# 1_Main.net
KiCad netlist of a schematic drawn in EAGLE
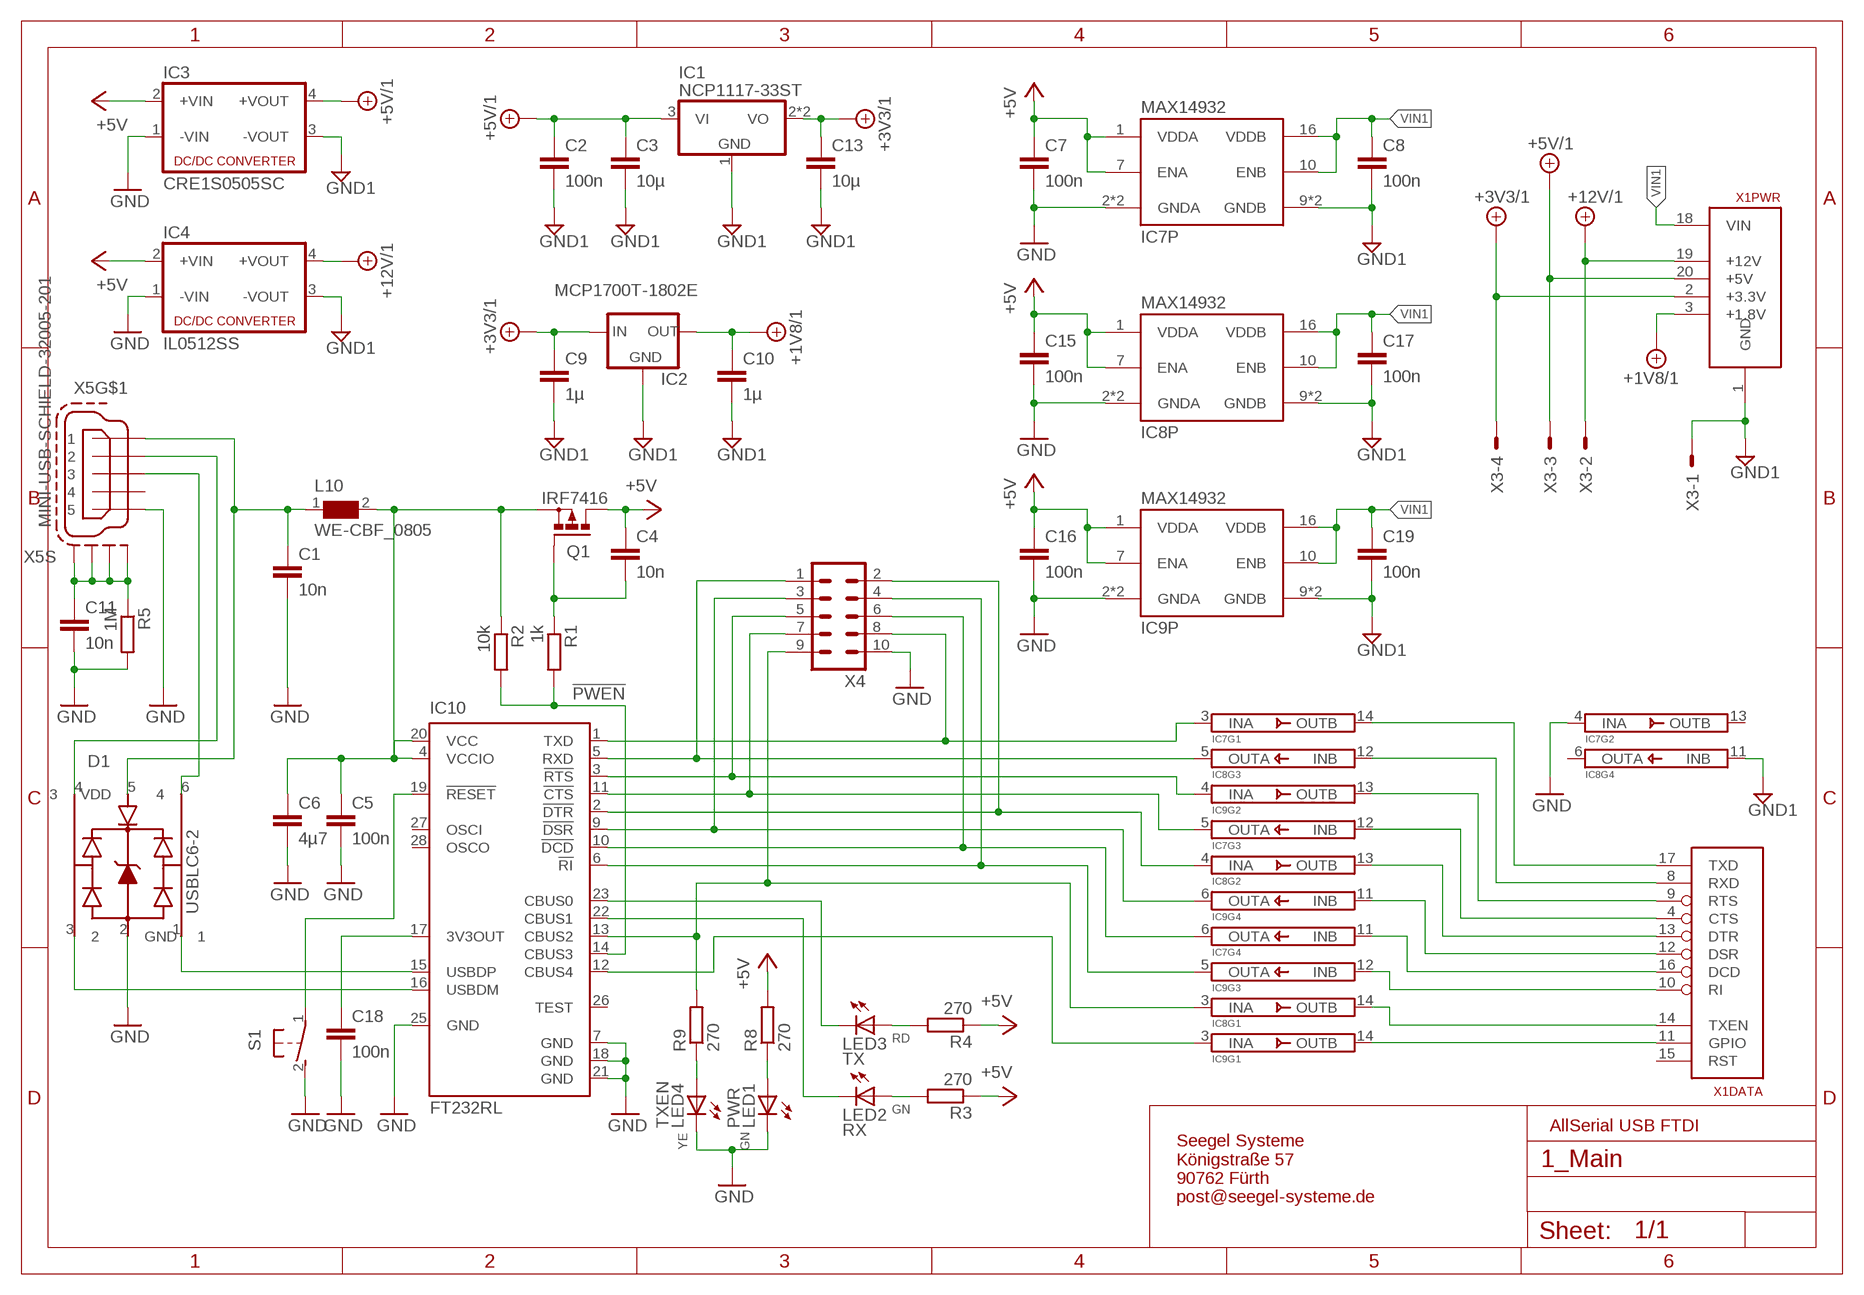
[diagram p0: schematic, sheet 1]

(export (version "E")
  (design (tool "Eeschema 10.0.6"))
  (components
    (comp (ref "C1")
      (value "10n")
      (footprint "eagle-import:C0805")
      (libsource (lib "eagle-import") (part "C-EUC0805"))
    )
    (comp (ref "C2")
      (value "100n")
      (footprint "eagle-import:C0805")
      (libsource (lib "eagle-import") (part "C-EUC0805"))
    )
    (comp (ref "C3")
      (value "10µ")
      (footprint "eagle-import:C0805")
      (libsource (lib "eagle-import") (part "C-EUC0805"))
    )
    (comp (ref "C4")
      (value "10n")
      (footprint "eagle-import:C0805")
      (libsource (lib "eagle-import") (part "C-EUC0805"))
    )
    (comp (ref "C5")
      (value "100n")
      (footprint "eagle-import:C0805")
      (libsource (lib "eagle-import") (part "C-EUC0805"))
    )
    (comp (ref "C6")
      (value "4µ7")
      (footprint "eagle-import:C0805")
      (libsource (lib "eagle-import") (part "C-EUC0805"))
    )
    (comp (ref "C7")
      (value "100n")
      (footprint "eagle-import:C0805")
      (libsource (lib "eagle-import") (part "C-EUC0805"))
    )
    (comp (ref "C8")
      (value "100n")
      (footprint "eagle-import:C0805")
      (libsource (lib "eagle-import") (part "C-EUC0805"))
    )
    (comp (ref "C9")
      (value "1µ")
      (footprint "eagle-import:C0805")
      (libsource (lib "eagle-import") (part "C-EUC0805"))
    )
    (comp (ref "C10")
      (value "1µ")
      (footprint "eagle-import:C0805")
      (libsource (lib "eagle-import") (part "C-EUC0805"))
    )
    (comp (ref "C11")
      (value "10n")
      (footprint "eagle-import:C0805")
      (libsource (lib "eagle-import") (part "C-EUC0805"))
    )
    (comp (ref "C13")
      (value "10µ")
      (footprint "eagle-import:C0805")
      (libsource (lib "eagle-import") (part "C-EUC0805"))
    )
    (comp (ref "C15")
      (value "100n")
      (footprint "eagle-import:C0805")
      (libsource (lib "eagle-import") (part "C-EUC0805"))
    )
    (comp (ref "C16")
      (value "100n")
      (footprint "eagle-import:C0805")
      (libsource (lib "eagle-import") (part "C-EUC0805"))
    )
    (comp (ref "C17")
      (value "100n")
      (footprint "eagle-import:C0805")
      (libsource (lib "eagle-import") (part "C-EUC0805"))
    )
    (comp (ref "C18")
      (value "100n")
      (footprint "eagle-import:C0805")
      (libsource (lib "eagle-import") (part "C-EUC0805"))
    )
    (comp (ref "C19")
      (value "100n")
      (footprint "eagle-import:C0805")
      (libsource (lib "eagle-import") (part "C-EUC0805"))
    )
    (comp (ref "D1")
      (value "USBLC6-2")
      (footprint "eagle-import:WE-TVS_SOT23-6L")
      (libsource (lib "eagle-import") (part "WE-TVS_82400102"))
    )
    (comp (ref "IC1")
      (value "NCP1117-33ST")
      (footprint "eagle-import:SOT223")
      (libsource (lib "eagle-import") (part "NCP1117ST-33"))
    )
    (comp (ref "IC2")
      (value "MCP1700T-1802E")
      (footprint "eagle-import:SOT23")
      (libsource (lib "eagle-import") (part "MCP170X"))
    )
    (comp (ref "IC3")
      (value "CRE1S0505SC")
      (footprint "eagle-import:MURATA-SC")
      (libsource (lib "eagle-import") (part "CRE1S?SC0505"))
    )
    (comp (ref "IC4")
      (value "IL0512SS")
      (footprint "eagle-import:XPPOWER-SIP")
      (libsource (lib "eagle-import") (part "ILSS0512"))
    )
    (comp (ref "IC7")
      (value "MAX14932")
      (footprint "eagle-import:SO16")
      (libsource (lib "eagle-import") (part "MAX14932"))
    )
    (comp (ref "IC8")
      (value "MAX14932")
      (footprint "eagle-import:SO16")
      (libsource (lib "eagle-import") (part "MAX14932"))
    )
    (comp (ref "IC9")
      (value "MAX14932")
      (footprint "eagle-import:SO16")
      (libsource (lib "eagle-import") (part "MAX14932"))
    )
    (comp (ref "IC10")
      (value "FT232RL")
      (footprint "eagle-import:SSOP28")
      (libsource (lib "eagle-import") (part "FT232RL"))
    )
    (comp (ref "L10")
      (value "WE-CBF_0805")
      (footprint "eagle-import:0805")
      (libsource (lib "eagle-import") (part "WE-CBF_0805"))
    )
    (comp (ref "LED1")
      (value "PWR")
      (footprint "eagle-import:CHIPLED_0603")
      (fields (field (name "COLOR") "GN"))
      (libsource (lib "eagle-import") (part "LEDCHIPLED_0603"))
    )
    (comp (ref "LED2")
      (value "RX")
      (footprint "eagle-import:CHIPLED_0603")
      (fields (field (name "COLOR") "GN"))
      (libsource (lib "eagle-import") (part "LEDCHIPLED_0603"))
    )
    (comp (ref "LED3")
      (value "TX")
      (footprint "eagle-import:CHIPLED_0603")
      (fields (field (name "COLOR") "RD"))
      (libsource (lib "eagle-import") (part "LEDCHIPLED_0603"))
    )
    (comp (ref "LED4")
      (value "TXEN")
      (footprint "eagle-import:CHIPLED_0603")
      (fields (field (name "COLOR") "YE"))
      (libsource (lib "eagle-import") (part "LEDCHIPLED_0603"))
    )
    (comp (ref "Q1")
      (value "IRF7416")
      (footprint "eagle-import:SO-08")
      (libsource (lib "eagle-import") (part "P-MOSFET-SO8"))
    )
    (comp (ref "R1")
      (value "1k")
      (footprint "eagle-import:R0805")
      (libsource (lib "eagle-import") (part "R-EU_R0805"))
    )
    (comp (ref "R2")
      (value "10k")
      (footprint "eagle-import:R0805")
      (libsource (lib "eagle-import") (part "R-EU_R0805"))
    )
    (comp (ref "R3")
      (value "270")
      (footprint "eagle-import:R0805")
      (libsource (lib "eagle-import") (part "R-EU_R0805"))
    )
    (comp (ref "R4")
      (value "270")
      (footprint "eagle-import:R0805")
      (libsource (lib "eagle-import") (part "R-EU_R0805"))
    )
    (comp (ref "R5")
      (value "1M")
      (footprint "eagle-import:R0805")
      (libsource (lib "eagle-import") (part "R-EU_R0805"))
    )
    (comp (ref "R8")
      (value "270")
      (footprint "eagle-import:R0805")
      (libsource (lib "eagle-import") (part "R-EU_R0805"))
    )
    (comp (ref "R9")
      (value "270")
      (footprint "eagle-import:R0805")
      (libsource (lib "eagle-import") (part "R-EU_R0805"))
    )
    (comp (ref "S1")
      (value "31-XX")
      (footprint "eagle-import:B3F-31XX")
      (fields (field (name "MPN") "B3F-3100"))
      (libsource (lib "eagle-import") (part "31-XX"))
    )
    (comp (ref "X1")
      (value "ALLSERIALMASTERMM")
      (footprint "eagle-import:MAIN-THT")
      (libsource (lib "eagle-import") (part "ALLSERIALMASTERMM"))
    )
    (comp (ref "X3")
      (value "AKL18X-04W")
      (footprint "eagle-import:AKL182-04")
      (libsource (lib "eagle-import") (part "AKL18X-04W"))
    )
    (comp (ref "X4")
      (value "ML10")
      (footprint "eagle-import:ML10")
      (libsource (lib "eagle-import") (part "ML10"))
    )
    (comp (ref "X5")
      (value "MINI-USB-SCHIELD-32005-201")
      (footprint "eagle-import:32005-201")
      (libsource (lib "eagle-import") (part "MINI-USB-SCHIELD-32005-201"))
    )
  )
  (nets
    (net (code "1") (name "+1V8{slash}1") (class "Default")
      (node (ref "C10") (pin "1") (pinfunction "1_1") (pintype "passive"))
      (node (ref "IC2") (pin "2") (pinfunction "OUT_2") (pintype "passive"))
      (node (ref "X1") (pin "3") (pinfunction "+1.8V_3") (pintype "bidirectional"))
    )
    (net (code "2") (name "+3V3{slash}1") (class "Default")
      (node (ref "C13") (pin "1") (pinfunction "1_1") (pintype "passive"))
      (node (ref "C9") (pin "1") (pinfunction "1_1") (pintype "passive"))
      (node (ref "IC1") (pin "2") (pinfunction "VO_2") (pintype "passive"))
      (node (ref "IC1") (pin "4") (pinfunction "VO_4") (pintype "passive"))
      (node (ref "IC2") (pin "3") (pinfunction "IN_3") (pintype "input"))
      (node (ref "X1") (pin "2") (pinfunction "+3.3V_2") (pintype "bidirectional"))
      (node (ref "X3") (pin "P$4") (pinfunction "S_P$4") (pintype "passive"))
    )
    (net (code "3") (name "+5V") (class "Default")
      (node (ref "C15") (pin "1") (pinfunction "1_1") (pintype "passive"))
      (node (ref "C16") (pin "1") (pinfunction "1_1") (pintype "passive"))
      (node (ref "C4") (pin "1") (pinfunction "1_1") (pintype "passive"))
      (node (ref "C7") (pin "1") (pinfunction "1_1") (pintype "passive"))
      (node (ref "IC3") (pin "2") (pinfunction "+VIN_2") (pintype "passive"))
      (node (ref "IC4") (pin "2") (pinfunction "+VIN_2") (pintype "passive"))
      (node (ref "IC7") (pin "1") (pinfunction "VDDA_1") (pintype "power_in"))
      (node (ref "IC7") (pin "7") (pinfunction "ENA_7") (pintype "input"))
      (node (ref "IC8") (pin "1") (pinfunction "VDDA_1") (pintype "power_in"))
      (node (ref "IC8") (pin "7") (pinfunction "ENA_7") (pintype "input"))
      (node (ref "IC9") (pin "1") (pinfunction "VDDA_1") (pintype "power_in"))
      (node (ref "IC9") (pin "7") (pinfunction "ENA_7") (pintype "input"))
      (node (ref "Q1") (pin "5") (pinfunction "D_5") (pintype "passive"))
      (node (ref "Q1") (pin "6") (pinfunction "D_6") (pintype "passive"))
      (node (ref "Q1") (pin "7") (pinfunction "D_7") (pintype "passive"))
      (node (ref "Q1") (pin "8") (pinfunction "D_8") (pintype "passive"))
      (node (ref "R3") (pin "1") (pinfunction "1_1") (pintype "passive"))
      (node (ref "R4") (pin "1") (pinfunction "1_1") (pintype "passive"))
      (node (ref "R8") (pin "2") (pinfunction "2_2") (pintype "passive"))
    )
    (net (code "4") (name "+5V{slash}1") (class "Default")
      (node (ref "C2") (pin "1") (pinfunction "1_1") (pintype "passive"))
      (node (ref "C3") (pin "1") (pinfunction "1_1") (pintype "passive"))
      (node (ref "IC1") (pin "3") (pinfunction "VI_3") (pintype "input"))
      (node (ref "IC3") (pin "4") (pinfunction "+VOUT_4") (pintype "passive"))
      (node (ref "X1") (pin "20") (pinfunction "+5V_20") (pintype "bidirectional"))
      (node (ref "X3") (pin "P$3") (pinfunction "S_P$3") (pintype "passive"))
    )
    (net (code "5") (name "+12V{slash}1") (class "Default")
      (node (ref "IC4") (pin "4") (pinfunction "+VOUT_4") (pintype "passive"))
      (node (ref "X1") (pin "19") (pinfunction "+12V_19") (pintype "bidirectional"))
      (node (ref "X3") (pin "P$2") (pinfunction "S_P$2") (pintype "passive"))
    )
    (net (code "6") (name "/~{PWEN}") (class "Default")
      (node (ref "IC10") (pin "14") (pinfunction "CBUS3_14") (pintype "bidirectional"))
      (node (ref "R1") (pin "2") (pinfunction "2_2") (pintype "passive"))
      (node (ref "R2") (pin "2") (pinfunction "2_2") (pintype "passive"))
    )
    (net (code "7") (name "GND") (class "Default")
      (node (ref "C1") (pin "2") (pinfunction "2_2") (pintype "passive"))
      (node (ref "C11") (pin "2") (pinfunction "2_2") (pintype "passive"))
      (node (ref "C15") (pin "2") (pinfunction "2_2") (pintype "passive"))
      (node (ref "C16") (pin "2") (pinfunction "2_2") (pintype "passive"))
      (node (ref "C18") (pin "2") (pinfunction "2_2") (pintype "passive"))
      (node (ref "C5") (pin "2") (pinfunction "2_2") (pintype "passive"))
      (node (ref "C6") (pin "2") (pinfunction "2_2") (pintype "passive"))
      (node (ref "C7") (pin "2") (pinfunction "2_2") (pintype "passive"))
      (node (ref "D1") (pin "2") (pinfunction "GND_2") (pintype "power_in"))
      (node (ref "IC10") (pin "18") (pinfunction "GND_18") (pintype "power_in"))
      (node (ref "IC10") (pin "21") (pinfunction "GND_21") (pintype "power_in"))
      (node (ref "IC10") (pin "25") (pinfunction "GND_25") (pintype "power_in"))
      (node (ref "IC10") (pin "7") (pinfunction "GND_7") (pintype "power_in"))
      (node (ref "IC3") (pin "1") (pinfunction "-VIN_1") (pintype "passive"))
      (node (ref "IC4") (pin "1") (pinfunction "-VIN_1") (pintype "passive"))
      (node (ref "IC7") (pin "2") (pinfunction "GNDA_2") (pintype "power_in"))
      (node (ref "IC7") (pin "4") (pinfunction "INA_4") (pintype "input"))
      (node (ref "IC7") (pin "8") (pinfunction "GNDA_8") (pintype "power_in"))
      (node (ref "IC8") (pin "2") (pinfunction "GNDA_2") (pintype "power_in"))
      (node (ref "IC8") (pin "8") (pinfunction "GNDA_8") (pintype "power_in"))
      (node (ref "IC9") (pin "2") (pinfunction "GNDA_2") (pintype "power_in"))
      (node (ref "IC9") (pin "8") (pinfunction "GNDA_8") (pintype "power_in"))
      (node (ref "LED1") (pin "C") (pinfunction "C_C") (pintype "passive"))
      (node (ref "LED4") (pin "C") (pinfunction "C_C") (pintype "passive"))
      (node (ref "R5") (pin "2") (pinfunction "2_2") (pintype "passive"))
      (node (ref "S1") (pin "2") (pinfunction "S_2") (pintype "passive"))
      (node (ref "X4") (pin "10") (pinfunction "10_10") (pintype "passive"))
      (node (ref "X5") (pin "5") (pinfunction "5_5") (pintype "passive"))
    )
    (net (code "8") (name "GND1") (class "Default")
      (node (ref "C10") (pin "2") (pinfunction "2_2") (pintype "passive"))
      (node (ref "C13") (pin "2") (pinfunction "2_2") (pintype "passive"))
      (node (ref "C17") (pin "2") (pinfunction "2_2") (pintype "passive"))
      (node (ref "C19") (pin "2") (pinfunction "2_2") (pintype "passive"))
      (node (ref "C2") (pin "2") (pinfunction "2_2") (pintype "passive"))
      (node (ref "C3") (pin "2") (pinfunction "2_2") (pintype "passive"))
      (node (ref "C8") (pin "2") (pinfunction "2_2") (pintype "passive"))
      (node (ref "C9") (pin "2") (pinfunction "2_2") (pintype "passive"))
      (node (ref "IC1") (pin "1") (pinfunction "GND_1") (pintype "passive"))
      (node (ref "IC2") (pin "1") (pinfunction "GND_1") (pintype "input"))
      (node (ref "IC3") (pin "3") (pinfunction "-VOUT_3") (pintype "passive"))
      (node (ref "IC4") (pin "3") (pinfunction "-VOUT_3") (pintype "passive"))
      (node (ref "IC7") (pin "15") (pinfunction "GNDB_15") (pintype "power_in"))
      (node (ref "IC7") (pin "9") (pinfunction "GNDB_9") (pintype "power_in"))
      (node (ref "IC8") (pin "11") (pinfunction "INB_11") (pintype "input"))
      (node (ref "IC8") (pin "15") (pinfunction "GNDB_15") (pintype "power_in"))
      (node (ref "IC8") (pin "9") (pinfunction "GNDB_9") (pintype "power_in"))
      (node (ref "IC9") (pin "15") (pinfunction "GNDB_15") (pintype "power_in"))
      (node (ref "IC9") (pin "9") (pinfunction "GNDB_9") (pintype "power_in"))
      (node (ref "X1") (pin "1") (pinfunction "GND_1") (pintype "bidirectional"))
      (node (ref "X3") (pin "P$1") (pinfunction "S_P$1") (pintype "passive"))
    )
    (net (code "9") (name "Net-(D1-2)") (class "Default")
      (node (ref "D1") (pin "3") (pinfunction "2_3") (pintype "passive"))
      (node (ref "IC10") (pin "16") (pinfunction "USBDM_16") (pintype "bidirectional"))
    )
    (net (code "10") (name "Net-(D1-3)") (class "Default")
      (node (ref "D1") (pin "4") (pinfunction "3_4") (pintype "passive"))
      (node (ref "X5") (pin "2") (pinfunction "2_2") (pintype "passive"))
    )
    (net (code "11") (name "Net-(D1-4)") (class "Default")
      (node (ref "D1") (pin "6") (pinfunction "4_6") (pintype "passive"))
      (node (ref "X5") (pin "3") (pinfunction "3_3") (pintype "passive"))
    )
    (net (code "12") (name "Net-(D1-VDD)") (class "Default")
      (node (ref "C1") (pin "1") (pinfunction "1_1") (pintype "passive"))
      (node (ref "D1") (pin "5") (pinfunction "VDD_5") (pintype "power_in"))
      (node (ref "L10") (pin "1") (pinfunction "1_1") (pintype "passive"))
      (node (ref "X5") (pin "1") (pinfunction "1_1") (pintype "passive"))
    )
    (net (code "13") (name "Net-(IC7A-OUTB)") (class "Default")
      (node (ref "IC7") (pin "14") (pinfunction "OUTB_14") (pintype "output"))
      (node (ref "X1") (pin "17") (pinfunction "TXD_17") (pintype "input"))
    )
    (net (code "14") (name "Net-(IC7C-INB)") (class "Default")
      (node (ref "IC7") (pin "12") (pinfunction "INB_12") (pintype "input"))
      (node (ref "X1") (pin "4") (pinfunction "CTS_4") (pintype "output"))
    )
    (net (code "15") (name "Net-(IC7D-INB)") (class "Default")
      (node (ref "IC7") (pin "11") (pinfunction "INB_11") (pintype "input"))
      (node (ref "X1") (pin "16") (pinfunction "DCD_16") (pintype "output"))
    )
    (net (code "16") (name "Net-(IC8A-OUTB)") (class "Default")
      (node (ref "IC8") (pin "14") (pinfunction "OUTB_14") (pintype "output"))
      (node (ref "X1") (pin "14") (pinfunction "TXEN_14") (pintype "input"))
    )
    (net (code "17") (name "Net-(IC8B-OUTB)") (class "Default")
      (node (ref "IC8") (pin "13") (pinfunction "OUTB_13") (pintype "output"))
      (node (ref "X1") (pin "13") (pinfunction "DTR_13") (pintype "input"))
    )
    (net (code "18") (name "Net-(IC8C-INB)") (class "Default")
      (node (ref "IC8") (pin "12") (pinfunction "INB_12") (pintype "input"))
      (node (ref "X1") (pin "8") (pinfunction "RXD_8") (pintype "output"))
    )
    (net (code "19") (name "Net-(IC9A-OUTB)") (class "Default")
      (node (ref "IC9") (pin "14") (pinfunction "OUTB_14") (pintype "output"))
      (node (ref "X1") (pin "11") (pinfunction "GPIO_11") (pintype "bidirectional"))
    )
    (net (code "20") (name "Net-(IC9B-OUTB)") (class "Default")
      (node (ref "IC9") (pin "13") (pinfunction "OUTB_13") (pintype "output"))
      (node (ref "X1") (pin "9") (pinfunction "RTS_9") (pintype "input"))
    )
    (net (code "21") (name "Net-(IC9C-INB)") (class "Default")
      (node (ref "IC9") (pin "12") (pinfunction "INB_12") (pintype "input"))
      (node (ref "X1") (pin "10") (pinfunction "RI_10") (pintype "output"))
    )
    (net (code "22") (name "Net-(IC9D-INB)") (class "Default")
      (node (ref "IC9") (pin "11") (pinfunction "INB_11") (pintype "input"))
      (node (ref "X1") (pin "12") (pinfunction "DSR_12") (pintype "output"))
    )
    (net (code "23") (name "Net-(IC10-3V3OUT)") (class "Default")
      (node (ref "C18") (pin "1") (pinfunction "1_1") (pintype "passive"))
      (node (ref "IC10") (pin "17") (pinfunction "3V3OUT_17") (pintype "output"))
    )
    (net (code "24") (name "Net-(IC10-CBUS0)") (class "Default")
      (node (ref "IC10") (pin "23") (pinfunction "CBUS0_23") (pintype "bidirectional"))
      (node (ref "LED3") (pin "C") (pinfunction "C_C") (pintype "passive"))
    )
    (net (code "25") (name "Net-(IC10-CBUS1)") (class "Default")
      (node (ref "IC10") (pin "22") (pinfunction "CBUS1_22") (pintype "bidirectional"))
      (node (ref "LED2") (pin "C") (pinfunction "C_C") (pintype "passive"))
    )
    (net (code "26") (name "Net-(IC10-CBUS2)") (class "Default")
      (node (ref "IC10") (pin "13") (pinfunction "CBUS2_13") (pintype "bidirectional"))
      (node (ref "IC8") (pin "3") (pinfunction "INA_3") (pintype "input"))
      (node (ref "R9") (pin "2") (pinfunction "2_2") (pintype "passive"))
      (node (ref "X4") (pin "9") (pinfunction "9_9") (pintype "passive"))
    )
    (net (code "27") (name "Net-(IC10-CBUS4)") (class "Default")
      (node (ref "IC10") (pin "12") (pinfunction "CBUS4_12") (pintype "bidirectional"))
      (node (ref "IC9") (pin "3") (pinfunction "INA_3") (pintype "input"))
    )
    (net (code "28") (name "Net-(IC10-RXD)") (class "Default")
      (node (ref "IC10") (pin "5") (pinfunction "RXD_5") (pintype "input"))
      (node (ref "IC8") (pin "5") (pinfunction "OUTA_5") (pintype "output"))
      (node (ref "X4") (pin "1") (pinfunction "1_1") (pintype "passive"))
    )
    (net (code "29") (name "Net-(IC10-TXD)") (class "Default")
      (node (ref "IC10") (pin "1") (pinfunction "TXD_1") (pintype "output"))
      (node (ref "IC7") (pin "3") (pinfunction "INA_3") (pintype "input"))
      (node (ref "X4") (pin "8") (pinfunction "8_8") (pintype "passive"))
    )
    (net (code "30") (name "Net-(IC10-USBDP)") (class "Default")
      (node (ref "D1") (pin "1") (pinfunction "1_1") (pintype "passive"))
      (node (ref "IC10") (pin "15") (pinfunction "USBDP_15") (pintype "bidirectional"))
    )
    (net (code "31") (name "Net-(IC10-VCC)") (class "Default")
      (node (ref "C5") (pin "1") (pinfunction "1_1") (pintype "passive"))
      (node (ref "C6") (pin "1") (pinfunction "1_1") (pintype "passive"))
      (node (ref "IC10") (pin "20") (pinfunction "VCC_20") (pintype "power_in"))
      (node (ref "IC10") (pin "4") (pinfunction "VCCIO_4") (pintype "power_in"))
      (node (ref "L10") (pin "2") (pinfunction "2_2") (pintype "passive"))
      (node (ref "Q1") (pin "1") (pinfunction "S_1") (pintype "passive"))
      (node (ref "Q1") (pin "2") (pinfunction "S_2") (pintype "passive"))
      (node (ref "Q1") (pin "3") (pinfunction "S_3") (pintype "passive"))
      (node (ref "R2") (pin "1") (pinfunction "1_1") (pintype "passive"))
    )
    (net (code "32") (name "Net-(IC10-~{CTS})") (class "Default")
      (node (ref "IC10") (pin "11") (pinfunction "~{CTS}_11") (pintype "input"))
      (node (ref "IC7") (pin "5") (pinfunction "OUTA_5") (pintype "output"))
      (node (ref "X4") (pin "7") (pinfunction "7_7") (pintype "passive"))
    )
    (net (code "33") (name "Net-(IC10-~{DCD})") (class "Default")
      (node (ref "IC10") (pin "10") (pinfunction "~{DCD}_10") (pintype "input"))
      (node (ref "IC7") (pin "6") (pinfunction "OUTA_6") (pintype "output"))
      (node (ref "X4") (pin "6") (pinfunction "6_6") (pintype "passive"))
    )
    (net (code "34") (name "Net-(IC10-~{DSR})") (class "Default")
      (node (ref "IC10") (pin "9") (pinfunction "~{DSR}_9") (pintype "input"))
      (node (ref "IC9") (pin "6") (pinfunction "OUTA_6") (pintype "output"))
      (node (ref "X4") (pin "3") (pinfunction "3_3") (pintype "passive"))
    )
    (net (code "35") (name "Net-(IC10-~{DTR})") (class "Default")
      (node (ref "IC10") (pin "2") (pinfunction "~{DTR}_2") (pintype "output"))
      (node (ref "IC8") (pin "4") (pinfunction "INA_4") (pintype "input"))
      (node (ref "X4") (pin "2") (pinfunction "2_2") (pintype "passive"))
    )
    (net (code "36") (name "Net-(IC10-~{RESET})") (class "Default")
      (node (ref "IC10") (pin "19") (pinfunction "~{RESET}_19") (pintype "input"))
      (node (ref "S1") (pin "1") (pinfunction "P_1") (pintype "passive"))
    )
    (net (code "37") (name "Net-(IC10-~{RI})") (class "Default")
      (node (ref "IC10") (pin "6") (pinfunction "~{RI}_6") (pintype "input"))
      (node (ref "IC9") (pin "5") (pinfunction "OUTA_5") (pintype "output"))
      (node (ref "X4") (pin "4") (pinfunction "4_4") (pintype "passive"))
    )
    (net (code "38") (name "Net-(IC10-~{RTS})") (class "Default")
      (node (ref "IC10") (pin "3") (pinfunction "~{RTS}_3") (pintype "output"))
      (node (ref "IC9") (pin "4") (pinfunction "INA_4") (pintype "input"))
      (node (ref "X4") (pin "5") (pinfunction "5_5") (pintype "passive"))
    )
    (net (code "39") (name "Net-(LED1-PadA)") (class "Default")
      (node (ref "LED1") (pin "A") (pinfunction "A_A") (pintype "passive"))
      (node (ref "R8") (pin "1") (pinfunction "1_1") (pintype "passive"))
    )
    (net (code "40") (name "Net-(LED2-PadA)") (class "Default")
      (node (ref "LED2") (pin "A") (pinfunction "A_A") (pintype "passive"))
      (node (ref "R3") (pin "2") (pinfunction "2_2") (pintype "passive"))
    )
    (net (code "41") (name "Net-(LED3-PadA)") (class "Default")
      (node (ref "LED3") (pin "A") (pinfunction "A_A") (pintype "passive"))
      (node (ref "R4") (pin "2") (pinfunction "2_2") (pintype "passive"))
    )
    (net (code "42") (name "Net-(LED4-PadA)") (class "Default")
      (node (ref "LED4") (pin "A") (pinfunction "A_A") (pintype "passive"))
      (node (ref "R9") (pin "1") (pinfunction "1_1") (pintype "passive"))
    )
    (net (code "43") (name "Net-(Q1-G)") (class "Default")
      (node (ref "C4") (pin "2") (pinfunction "2_2") (pintype "passive"))
      (node (ref "Q1") (pin "4") (pinfunction "G_4") (pintype "passive"))
      (node (ref "R1") (pin "1") (pinfunction "1_1") (pintype "passive"))
    )
    (net (code "44") (name "Net-(X5B-S1)") (class "Default")
      (node (ref "C11") (pin "1") (pinfunction "1_1") (pintype "passive"))
      (node (ref "R5") (pin "1") (pinfunction "1_1") (pintype "passive"))
      (node (ref "X5") (pin "M1") (pinfunction "S1_M1") (pintype "passive"))
      (node (ref "X5") (pin "M2") (pinfunction "S2_M2") (pintype "passive"))
      (node (ref "X5") (pin "M3") (pinfunction "S3_M3") (pintype "passive"))
      (node (ref "X5") (pin "M4") (pinfunction "S4_M4") (pintype "passive"))
    )
    (net (code "45") (name "VIN1") (class "Default")
      (node (ref "C17") (pin "1") (pinfunction "1_1") (pintype "passive"))
      (node (ref "C19") (pin "1") (pinfunction "1_1") (pintype "passive"))
      (node (ref "C8") (pin "1") (pinfunction "1_1") (pintype "passive"))
      (node (ref "IC7") (pin "10") (pinfunction "ENB_10") (pintype "input"))
      (node (ref "IC7") (pin "16") (pinfunction "VDDB_16") (pintype "power_in"))
      (node (ref "IC8") (pin "10") (pinfunction "ENB_10") (pintype "input"))
      (node (ref "IC8") (pin "16") (pinfunction "VDDB_16") (pintype "power_in"))
      (node (ref "IC9") (pin "10") (pinfunction "ENB_10") (pintype "input"))
      (node (ref "IC9") (pin "16") (pinfunction "VDDB_16") (pintype "power_in"))
      (node (ref "X1") (pin "18") (pinfunction "VIN_18") (pintype "bidirectional"))
    )
    (net (code "46") (name "unconnected-(IC7B-OUTB-Pad13)") (class "Default")
      (node (ref "IC7") (pin "13") (pinfunction "OUTB_13") (pintype "output"))
    )
    (net (code "47") (name "unconnected-(IC8D-OUTA-Pad6)") (class "Default")
      (node (ref "IC8") (pin "6") (pinfunction "OUTA_6") (pintype "output"))
    )
    (net (code "48") (name "unconnected-(IC10-OSCI-Pad27)") (class "Default")
      (node (ref "IC10") (pin "27") (pinfunction "OSCI_27") (pintype "input"))
    )
    (net (code "49") (name "unconnected-(IC10-OSCO-Pad28)") (class "Default")
      (node (ref "IC10") (pin "28") (pinfunction "OSCO_28") (pintype "output"))
    )
    (net (code "50") (name "unconnected-(IC10-TEST-Pad26)") (class "Default")
      (node (ref "IC10") (pin "26") (pinfunction "TEST_26") (pintype "input"))
    )
    (net (code "51") (name "unconnected-(X1A-RST-Pad15)") (class "Default")
      (node (ref "X1") (pin "15") (pinfunction "RST_15") (pintype "bidirectional"))
    )
    (net (code "52") (name "unconnected-(X5-Pad4)") (class "Default")
      (node (ref "X5") (pin "4") (pinfunction "4_4") (pintype "passive"))
    )
  )
)
